# swizzle.net
KiCad netlist of a schematic drawn in EAGLE
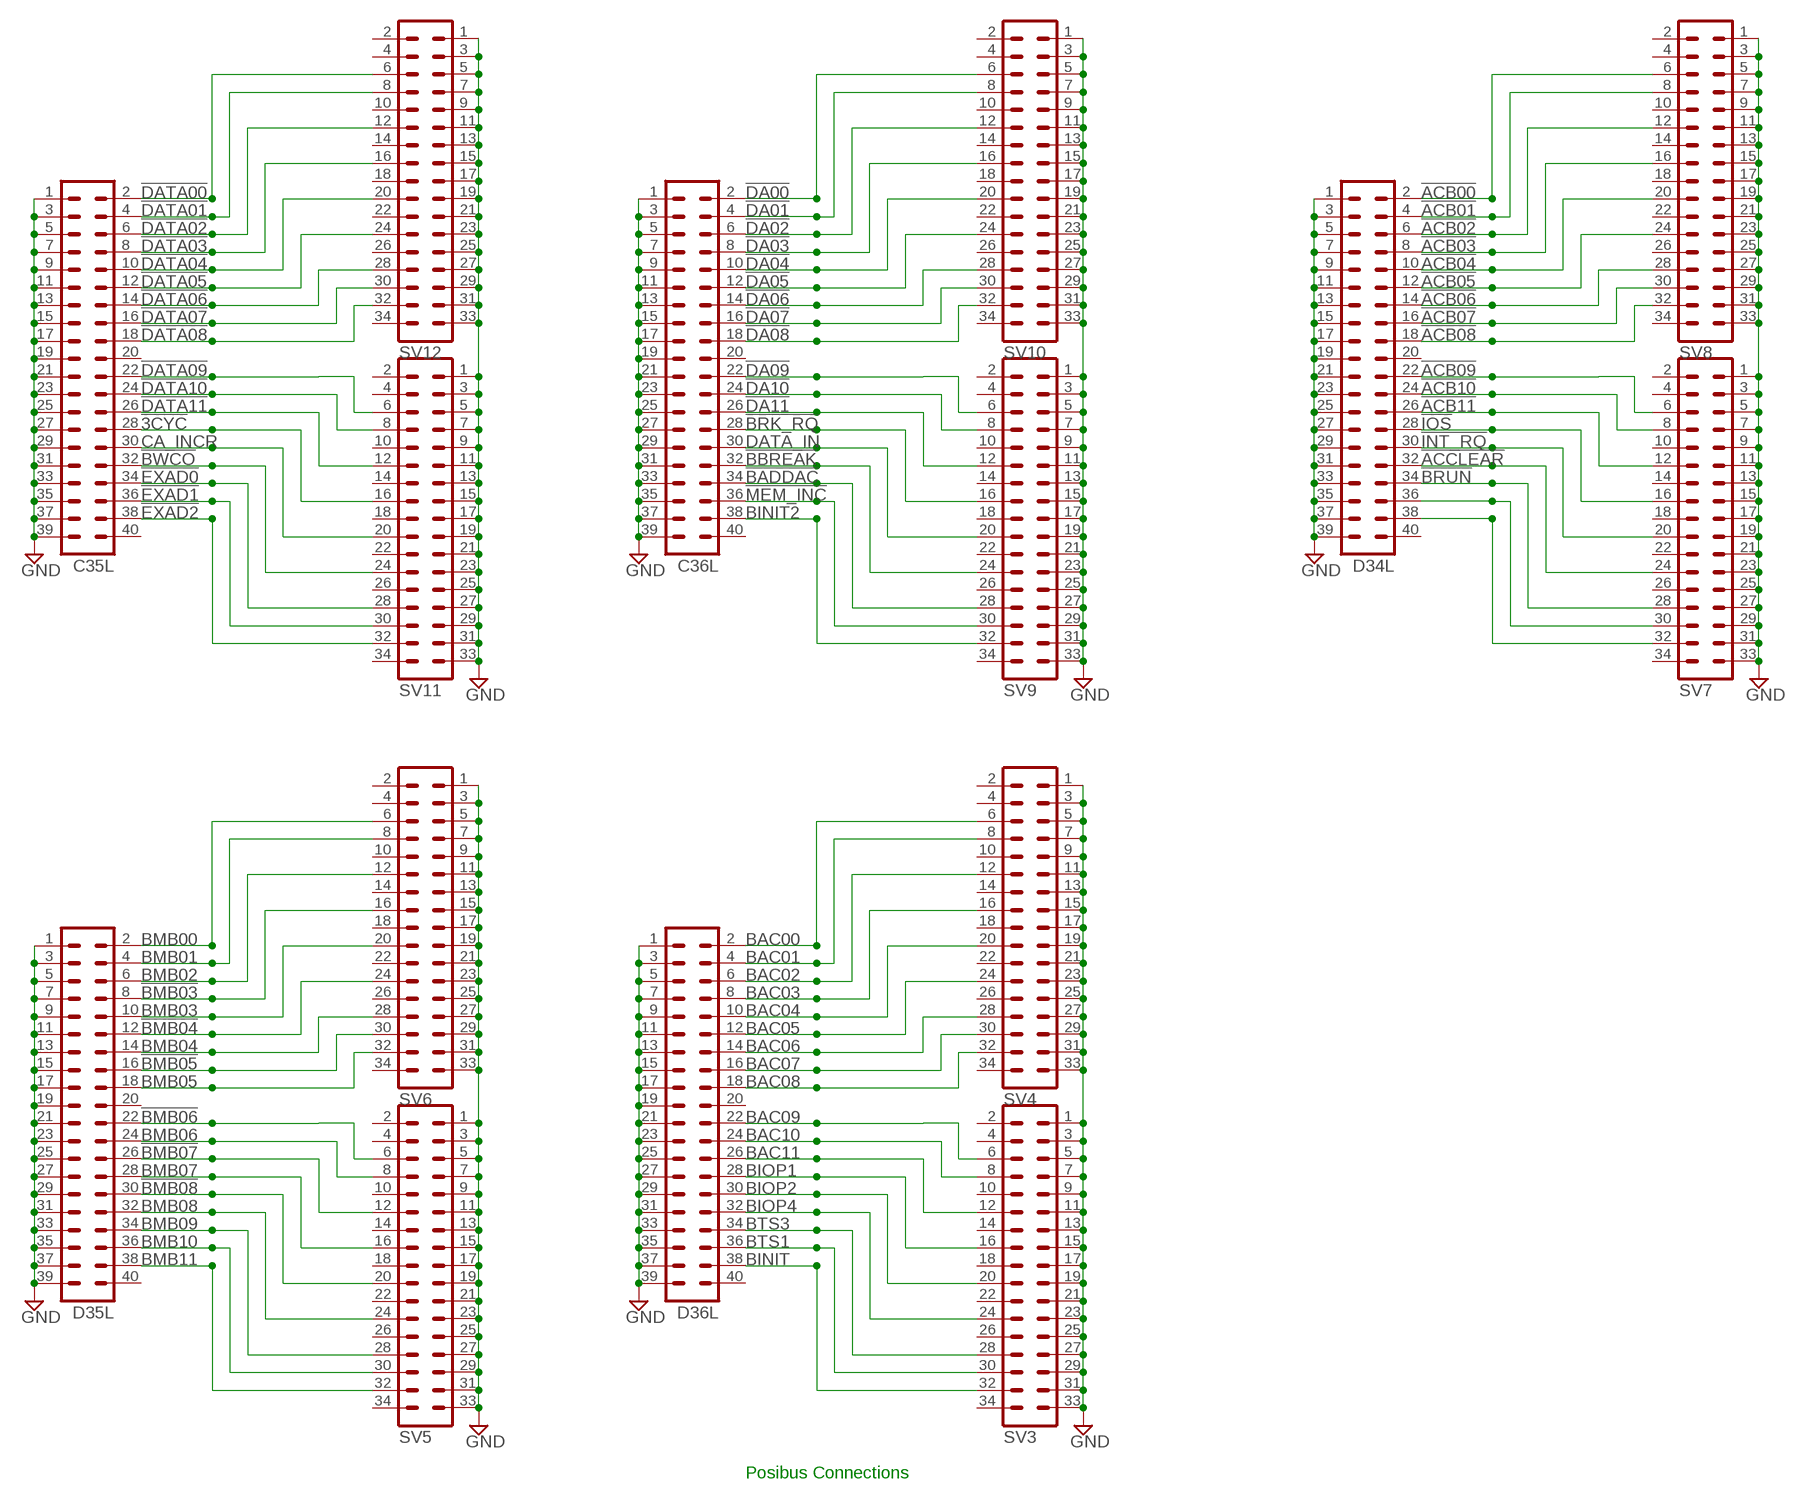
[diagram p0: schematic, sheet 1]

(export (version "E")
  (design (tool "Eeschema 10.0.6"))
  (components
    (comp (ref "C35L")
      (value "MA20-2")
      (footprint "eagle-import:MA20-2")
      (libsource (lib "eagle-import") (part "MA20-2"))
    )
    (comp (ref "C36L")
      (value "MA20-2")
      (footprint "eagle-import:MA20-2")
      (libsource (lib "eagle-import") (part "MA20-2"))
    )
    (comp (ref "D34L")
      (value "MA20-2")
      (footprint "eagle-import:MA20-2")
      (libsource (lib "eagle-import") (part "MA20-2"))
    )
    (comp (ref "D35L")
      (value "MA20-2")
      (footprint "eagle-import:MA20-2")
      (libsource (lib "eagle-import") (part "MA20-2"))
    )
    (comp (ref "D36L")
      (value "MA20-2")
      (footprint "eagle-import:MA20-2")
      (libsource (lib "eagle-import") (part "MA20-2"))
    )
    (comp (ref "SV3")
      (value "MA17-2")
      (footprint "eagle-import:MA17-2")
      (libsource (lib "eagle-import") (part "MA17-2"))
    )
    (comp (ref "SV4")
      (value "MA17-2")
      (footprint "eagle-import:MA17-2")
      (libsource (lib "eagle-import") (part "MA17-2"))
    )
    (comp (ref "SV5")
      (value "MA17-2")
      (footprint "eagle-import:MA17-2")
      (libsource (lib "eagle-import") (part "MA17-2"))
    )
    (comp (ref "SV6")
      (value "MA17-2")
      (footprint "eagle-import:MA17-2")
      (libsource (lib "eagle-import") (part "MA17-2"))
    )
    (comp (ref "SV7")
      (value "MA17-2")
      (footprint "eagle-import:MA17-2")
      (libsource (lib "eagle-import") (part "MA17-2"))
    )
    (comp (ref "SV8")
      (value "MA17-2")
      (footprint "eagle-import:MA17-2")
      (libsource (lib "eagle-import") (part "MA17-2"))
    )
    (comp (ref "SV9")
      (value "MA17-2")
      (footprint "eagle-import:MA17-2")
      (libsource (lib "eagle-import") (part "MA17-2"))
    )
    (comp (ref "SV10")
      (value "MA17-2")
      (footprint "eagle-import:MA17-2")
      (libsource (lib "eagle-import") (part "MA17-2"))
    )
    (comp (ref "SV11")
      (value "MA17-2")
      (footprint "eagle-import:MA17-2")
      (libsource (lib "eagle-import") (part "MA17-2"))
    )
    (comp (ref "SV12")
      (value "MA17-2")
      (footprint "eagle-import:MA17-2")
      (libsource (lib "eagle-import") (part "MA17-2"))
    )
  )
  (nets
    (net (code "1") (name "/BAC00") (class "Default")
      (node (ref "D36L") (pin "2") (pinfunction "2_2") (pintype "passive"))
      (node (ref "SV4") (pin "6") (pinfunction "6_6") (pintype "passive"))
    )
    (net (code "2") (name "/BAC01") (class "Default")
      (node (ref "D36L") (pin "4") (pinfunction "4_4") (pintype "passive"))
      (node (ref "SV4") (pin "8") (pinfunction "8_8") (pintype "passive"))
    )
    (net (code "3") (name "/BAC02") (class "Default")
      (node (ref "D36L") (pin "6") (pinfunction "6_6") (pintype "passive"))
      (node (ref "SV4") (pin "12") (pinfunction "12_12") (pintype "passive"))
    )
    (net (code "4") (name "/BAC03") (class "Default")
      (node (ref "D36L") (pin "8") (pinfunction "8_8") (pintype "passive"))
      (node (ref "SV4") (pin "16") (pinfunction "16_16") (pintype "passive"))
    )
    (net (code "5") (name "/BAC04") (class "Default")
      (node (ref "D36L") (pin "10") (pinfunction "10_10") (pintype "passive"))
      (node (ref "SV4") (pin "20") (pinfunction "20_20") (pintype "passive"))
    )
    (net (code "6") (name "/BAC05") (class "Default")
      (node (ref "D36L") (pin "12") (pinfunction "12_12") (pintype "passive"))
      (node (ref "SV4") (pin "24") (pinfunction "24_24") (pintype "passive"))
    )
    (net (code "7") (name "/BAC06") (class "Default")
      (node (ref "D36L") (pin "14") (pinfunction "14_14") (pintype "passive"))
      (node (ref "SV4") (pin "28") (pinfunction "28_28") (pintype "passive"))
    )
    (net (code "8") (name "/BAC07") (class "Default")
      (node (ref "D36L") (pin "16") (pinfunction "16_16") (pintype "passive"))
      (node (ref "SV4") (pin "30") (pinfunction "30_30") (pintype "passive"))
    )
    (net (code "9") (name "/BAC08") (class "Default")
      (node (ref "D36L") (pin "18") (pinfunction "18_18") (pintype "passive"))
      (node (ref "SV4") (pin "32") (pinfunction "32_32") (pintype "passive"))
    )
    (net (code "10") (name "/BAC09") (class "Default")
      (node (ref "D36L") (pin "22") (pinfunction "22_22") (pintype "passive"))
      (node (ref "SV3") (pin "6") (pinfunction "6_6") (pintype "passive"))
    )
    (net (code "11") (name "/BAC10") (class "Default")
      (node (ref "D36L") (pin "24") (pinfunction "24_24") (pintype "passive"))
      (node (ref "SV3") (pin "8") (pinfunction "8_8") (pintype "passive"))
    )
    (net (code "12") (name "/BAC11") (class "Default")
      (node (ref "D36L") (pin "26") (pinfunction "26_26") (pintype "passive"))
      (node (ref "SV3") (pin "12") (pinfunction "12_12") (pintype "passive"))
    )
    (net (code "13") (name "/BINIT") (class "Default")
      (node (ref "D36L") (pin "38") (pinfunction "38_38") (pintype "passive"))
      (node (ref "SV3") (pin "32") (pinfunction "32_32") (pintype "passive"))
    )
    (net (code "14") (name "/BINIT2") (class "Default")
      (node (ref "C36L") (pin "38") (pinfunction "38_38") (pintype "passive"))
      (node (ref "SV9") (pin "32") (pinfunction "32_32") (pintype "passive"))
    )
    (net (code "15") (name "/BIOP1") (class "Default")
      (node (ref "D36L") (pin "28") (pinfunction "28_28") (pintype "passive"))
      (node (ref "SV3") (pin "16") (pinfunction "16_16") (pintype "passive"))
    )
    (net (code "16") (name "/BIOP2") (class "Default")
      (node (ref "D36L") (pin "30") (pinfunction "30_30") (pintype "passive"))
      (node (ref "SV3") (pin "20") (pinfunction "20_20") (pintype "passive"))
    )
    (net (code "17") (name "/BIOP4") (class "Default")
      (node (ref "D36L") (pin "32") (pinfunction "32_32") (pintype "passive"))
      (node (ref "SV3") (pin "24") (pinfunction "24_24") (pintype "passive"))
    )
    (net (code "18") (name "/BMB00") (class "Default")
      (node (ref "D35L") (pin "2") (pinfunction "2_2") (pintype "passive"))
      (node (ref "SV6") (pin "6") (pinfunction "6_6") (pintype "passive"))
    )
    (net (code "19") (name "/BMB01") (class "Default")
      (node (ref "D35L") (pin "4") (pinfunction "4_4") (pintype "passive"))
      (node (ref "SV6") (pin "8") (pinfunction "8_8") (pintype "passive"))
    )
    (net (code "20") (name "/BMB02") (class "Default")
      (node (ref "D35L") (pin "6") (pinfunction "6_6") (pintype "passive"))
      (node (ref "SV6") (pin "12") (pinfunction "12_12") (pintype "passive"))
    )
    (net (code "21") (name "/BMB03") (class "Default")
      (node (ref "D35L") (pin "10") (pinfunction "10_10") (pintype "passive"))
      (node (ref "SV6") (pin "20") (pinfunction "20_20") (pintype "passive"))
    )
    (net (code "22") (name "/BMB04") (class "Default")
      (node (ref "D35L") (pin "14") (pinfunction "14_14") (pintype "passive"))
      (node (ref "SV6") (pin "28") (pinfunction "28_28") (pintype "passive"))
    )
    (net (code "23") (name "/BMB05") (class "Default")
      (node (ref "D35L") (pin "18") (pinfunction "18_18") (pintype "passive"))
      (node (ref "SV6") (pin "32") (pinfunction "32_32") (pintype "passive"))
    )
    (net (code "24") (name "/BMB06") (class "Default")
      (node (ref "D35L") (pin "24") (pinfunction "24_24") (pintype "passive"))
      (node (ref "SV5") (pin "8") (pinfunction "8_8") (pintype "passive"))
    )
    (net (code "25") (name "/BMB07") (class "Default")
      (node (ref "D35L") (pin "28") (pinfunction "28_28") (pintype "passive"))
      (node (ref "SV5") (pin "16") (pinfunction "16_16") (pintype "passive"))
    )
    (net (code "26") (name "/BMB08") (class "Default")
      (node (ref "D35L") (pin "32") (pinfunction "32_32") (pintype "passive"))
      (node (ref "SV5") (pin "24") (pinfunction "24_24") (pintype "passive"))
    )
    (net (code "27") (name "/BMB09") (class "Default")
      (node (ref "D35L") (pin "34") (pinfunction "34_34") (pintype "passive"))
      (node (ref "SV5") (pin "28") (pinfunction "28_28") (pintype "passive"))
    )
    (net (code "28") (name "/BMB10") (class "Default")
      (node (ref "D35L") (pin "36") (pinfunction "36_36") (pintype "passive"))
      (node (ref "SV5") (pin "30") (pinfunction "30_30") (pintype "passive"))
    )
    (net (code "29") (name "/BMB11") (class "Default")
      (node (ref "D35L") (pin "38") (pinfunction "38_38") (pintype "passive"))
      (node (ref "SV5") (pin "32") (pinfunction "32_32") (pintype "passive"))
    )
    (net (code "30") (name "/BTS1") (class "Default")
      (node (ref "D36L") (pin "36") (pinfunction "36_36") (pintype "passive"))
      (node (ref "SV3") (pin "30") (pinfunction "30_30") (pintype "passive"))
    )
    (net (code "31") (name "/BTS3") (class "Default")
      (node (ref "D36L") (pin "34") (pinfunction "34_34") (pintype "passive"))
      (node (ref "SV3") (pin "28") (pinfunction "28_28") (pintype "passive"))
    )
    (net (code "32") (name "/CA_INCR") (class "Default")
      (node (ref "C35L") (pin "30") (pinfunction "30_30") (pintype "passive"))
      (node (ref "SV11") (pin "20") (pinfunction "20_20") (pintype "passive"))
    )
    (net (code "33") (name "/DATA_IN") (class "Default")
      (node (ref "C36L") (pin "30") (pinfunction "30_30") (pintype "passive"))
      (node (ref "SV9") (pin "20") (pinfunction "20_20") (pintype "passive"))
    )
    (net (code "34") (name "/~{3CYC}") (class "Default")
      (node (ref "C35L") (pin "28") (pinfunction "28_28") (pintype "passive"))
      (node (ref "SV11") (pin "16") (pinfunction "16_16") (pintype "passive"))
    )
    (net (code "35") (name "/~{ACB00}") (class "Default")
      (node (ref "D34L") (pin "2") (pinfunction "2_2") (pintype "passive"))
      (node (ref "SV8") (pin "6") (pinfunction "6_6") (pintype "passive"))
    )
    (net (code "36") (name "/~{ACB01}") (class "Default")
      (node (ref "D34L") (pin "4") (pinfunction "4_4") (pintype "passive"))
      (node (ref "SV8") (pin "8") (pinfunction "8_8") (pintype "passive"))
    )
    (net (code "37") (name "/~{ACB02}") (class "Default")
      (node (ref "D34L") (pin "6") (pinfunction "6_6") (pintype "passive"))
      (node (ref "SV8") (pin "12") (pinfunction "12_12") (pintype "passive"))
    )
    (net (code "38") (name "/~{ACB03}") (class "Default")
      (node (ref "D34L") (pin "8") (pinfunction "8_8") (pintype "passive"))
      (node (ref "SV8") (pin "16") (pinfunction "16_16") (pintype "passive"))
    )
    (net (code "39") (name "/~{ACB04}") (class "Default")
      (node (ref "D34L") (pin "10") (pinfunction "10_10") (pintype "passive"))
      (node (ref "SV8") (pin "20") (pinfunction "20_20") (pintype "passive"))
    )
    (net (code "40") (name "/~{ACB05}") (class "Default")
      (node (ref "D34L") (pin "12") (pinfunction "12_12") (pintype "passive"))
      (node (ref "SV8") (pin "24") (pinfunction "24_24") (pintype "passive"))
    )
    (net (code "41") (name "/~{ACB06}") (class "Default")
      (node (ref "D34L") (pin "14") (pinfunction "14_14") (pintype "passive"))
      (node (ref "SV8") (pin "28") (pinfunction "28_28") (pintype "passive"))
    )
    (net (code "42") (name "/~{ACB07}") (class "Default")
      (node (ref "D34L") (pin "16") (pinfunction "16_16") (pintype "passive"))
      (node (ref "SV8") (pin "30") (pinfunction "30_30") (pintype "passive"))
    )
    (net (code "43") (name "/~{ACB08}") (class "Default")
      (node (ref "D34L") (pin "18") (pinfunction "18_18") (pintype "passive"))
      (node (ref "SV8") (pin "32") (pinfunction "32_32") (pintype "passive"))
    )
    (net (code "44") (name "/~{ACB09}") (class "Default")
      (node (ref "D34L") (pin "22") (pinfunction "22_22") (pintype "passive"))
      (node (ref "SV7") (pin "6") (pinfunction "6_6") (pintype "passive"))
    )
    (net (code "45") (name "/~{ACB10}") (class "Default")
      (node (ref "D34L") (pin "24") (pinfunction "24_24") (pintype "passive"))
      (node (ref "SV7") (pin "8") (pinfunction "8_8") (pintype "passive"))
    )
    (net (code "46") (name "/~{ACB11}") (class "Default")
      (node (ref "D34L") (pin "26") (pinfunction "26_26") (pintype "passive"))
      (node (ref "SV7") (pin "12") (pinfunction "12_12") (pintype "passive"))
    )
    (net (code "47") (name "/~{ACCLEAR}") (class "Default")
      (node (ref "D34L") (pin "32") (pinfunction "32_32") (pintype "passive"))
      (node (ref "SV7") (pin "24") (pinfunction "24_24") (pintype "passive"))
    )
    (net (code "48") (name "/~{BADDAC}") (class "Default")
      (node (ref "C36L") (pin "34") (pinfunction "34_34") (pintype "passive"))
      (node (ref "SV9") (pin "28") (pinfunction "28_28") (pintype "passive"))
    )
    (net (code "49") (name "/~{BBREAK}") (class "Default")
      (node (ref "C36L") (pin "32") (pinfunction "32_32") (pintype "passive"))
      (node (ref "SV9") (pin "24") (pinfunction "24_24") (pintype "passive"))
    )
    (net (code "50") (name "/~{BMB03}") (class "Default")
      (node (ref "D35L") (pin "8") (pinfunction "8_8") (pintype "passive"))
      (node (ref "SV6") (pin "16") (pinfunction "16_16") (pintype "passive"))
    )
    (net (code "51") (name "/~{BMB04}") (class "Default")
      (node (ref "D35L") (pin "12") (pinfunction "12_12") (pintype "passive"))
      (node (ref "SV6") (pin "24") (pinfunction "24_24") (pintype "passive"))
    )
    (net (code "52") (name "/~{BMB05}") (class "Default")
      (node (ref "D35L") (pin "16") (pinfunction "16_16") (pintype "passive"))
      (node (ref "SV6") (pin "30") (pinfunction "30_30") (pintype "passive"))
    )
    (net (code "53") (name "/~{BMB06}") (class "Default")
      (node (ref "D35L") (pin "22") (pinfunction "22_22") (pintype "passive"))
      (node (ref "SV5") (pin "6") (pinfunction "6_6") (pintype "passive"))
    )
    (net (code "54") (name "/~{BMB07}") (class "Default")
      (node (ref "D35L") (pin "26") (pinfunction "26_26") (pintype "passive"))
      (node (ref "SV5") (pin "12") (pinfunction "12_12") (pintype "passive"))
    )
    (net (code "55") (name "/~{BMB08}") (class "Default")
      (node (ref "D35L") (pin "30") (pinfunction "30_30") (pintype "passive"))
      (node (ref "SV5") (pin "20") (pinfunction "20_20") (pintype "passive"))
    )
    (net (code "56") (name "/~{BRK_RQ}") (class "Default")
      (node (ref "C36L") (pin "28") (pinfunction "28_28") (pintype "passive"))
      (node (ref "SV9") (pin "16") (pinfunction "16_16") (pintype "passive"))
    )
    (net (code "57") (name "/~{BRUN}") (class "Default")
      (node (ref "D34L") (pin "34") (pinfunction "34_34") (pintype "passive"))
      (node (ref "SV7") (pin "28") (pinfunction "28_28") (pintype "passive"))
    )
    (net (code "58") (name "/~{BWCO}") (class "Default")
      (node (ref "C35L") (pin "32") (pinfunction "32_32") (pintype "passive"))
      (node (ref "SV11") (pin "24") (pinfunction "24_24") (pintype "passive"))
    )
    (net (code "59") (name "/~{DA00}") (class "Default")
      (node (ref "C36L") (pin "2") (pinfunction "2_2") (pintype "passive"))
      (node (ref "SV10") (pin "6") (pinfunction "6_6") (pintype "passive"))
    )
    (net (code "60") (name "/~{DA01}") (class "Default")
      (node (ref "C36L") (pin "4") (pinfunction "4_4") (pintype "passive"))
      (node (ref "SV10") (pin "8") (pinfunction "8_8") (pintype "passive"))
    )
    (net (code "61") (name "/~{DA02}") (class "Default")
      (node (ref "C36L") (pin "6") (pinfunction "6_6") (pintype "passive"))
      (node (ref "SV10") (pin "12") (pinfunction "12_12") (pintype "passive"))
    )
    (net (code "62") (name "/~{DA03}") (class "Default")
      (node (ref "C36L") (pin "8") (pinfunction "8_8") (pintype "passive"))
      (node (ref "SV10") (pin "16") (pinfunction "16_16") (pintype "passive"))
    )
    (net (code "63") (name "/~{DA04}") (class "Default")
      (node (ref "C36L") (pin "10") (pinfunction "10_10") (pintype "passive"))
      (node (ref "SV10") (pin "20") (pinfunction "20_20") (pintype "passive"))
    )
    (net (code "64") (name "/~{DA05}") (class "Default")
      (node (ref "C36L") (pin "12") (pinfunction "12_12") (pintype "passive"))
      (node (ref "SV10") (pin "24") (pinfunction "24_24") (pintype "passive"))
    )
    (net (code "65") (name "/~{DA06}") (class "Default")
      (node (ref "C36L") (pin "14") (pinfunction "14_14") (pintype "passive"))
      (node (ref "SV10") (pin "28") (pinfunction "28_28") (pintype "passive"))
    )
    (net (code "66") (name "/~{DA07}") (class "Default")
      (node (ref "C36L") (pin "16") (pinfunction "16_16") (pintype "passive"))
      (node (ref "SV10") (pin "30") (pinfunction "30_30") (pintype "passive"))
    )
    (net (code "67") (name "/~{DA08}") (class "Default")
      (node (ref "C36L") (pin "18") (pinfunction "18_18") (pintype "passive"))
      (node (ref "SV10") (pin "32") (pinfunction "32_32") (pintype "passive"))
    )
    (net (code "68") (name "/~{DA09}") (class "Default")
      (node (ref "C36L") (pin "22") (pinfunction "22_22") (pintype "passive"))
      (node (ref "SV9") (pin "6") (pinfunction "6_6") (pintype "passive"))
    )
    (net (code "69") (name "/~{DA10}") (class "Default")
      (node (ref "C36L") (pin "24") (pinfunction "24_24") (pintype "passive"))
      (node (ref "SV9") (pin "8") (pinfunction "8_8") (pintype "passive"))
    )
    (net (code "70") (name "/~{DA11}") (class "Default")
      (node (ref "C36L") (pin "26") (pinfunction "26_26") (pintype "passive"))
      (node (ref "SV9") (pin "12") (pinfunction "12_12") (pintype "passive"))
    )
    (net (code "71") (name "/~{DATA00}") (class "Default")
      (node (ref "C35L") (pin "2") (pinfunction "2_2") (pintype "passive"))
      (node (ref "SV12") (pin "6") (pinfunction "6_6") (pintype "passive"))
    )
    (net (code "72") (name "/~{DATA01}") (class "Default")
      (node (ref "C35L") (pin "4") (pinfunction "4_4") (pintype "passive"))
      (node (ref "SV12") (pin "8") (pinfunction "8_8") (pintype "passive"))
    )
    (net (code "73") (name "/~{DATA02}") (class "Default")
      (node (ref "C35L") (pin "6") (pinfunction "6_6") (pintype "passive"))
      (node (ref "SV12") (pin "12") (pinfunction "12_12") (pintype "passive"))
    )
    (net (code "74") (name "/~{DATA03}") (class "Default")
      (node (ref "C35L") (pin "8") (pinfunction "8_8") (pintype "passive"))
      (node (ref "SV12") (pin "16") (pinfunction "16_16") (pintype "passive"))
    )
    (net (code "75") (name "/~{DATA04}") (class "Default")
      (node (ref "C35L") (pin "10") (pinfunction "10_10") (pintype "passive"))
      (node (ref "SV12") (pin "20") (pinfunction "20_20") (pintype "passive"))
    )
    (net (code "76") (name "/~{DATA05}") (class "Default")
      (node (ref "C35L") (pin "12") (pinfunction "12_12") (pintype "passive"))
      (node (ref "SV12") (pin "24") (pinfunction "24_24") (pintype "passive"))
    )
    (net (code "77") (name "/~{DATA06}") (class "Default")
      (node (ref "C35L") (pin "14") (pinfunction "14_14") (pintype "passive"))
      (node (ref "SV12") (pin "28") (pinfunction "28_28") (pintype "passive"))
    )
    (net (code "78") (name "/~{DATA07}") (class "Default")
      (node (ref "C35L") (pin "16") (pinfunction "16_16") (pintype "passive"))
      (node (ref "SV12") (pin "30") (pinfunction "30_30") (pintype "passive"))
    )
    (net (code "79") (name "/~{DATA08}") (class "Default")
      (node (ref "C35L") (pin "18") (pinfunction "18_18") (pintype "passive"))
      (node (ref "SV12") (pin "32") (pinfunction "32_32") (pintype "passive"))
    )
    (net (code "80") (name "/~{DATA09}") (class "Default")
      (node (ref "C35L") (pin "22") (pinfunction "22_22") (pintype "passive"))
      (node (ref "SV11") (pin "6") (pinfunction "6_6") (pintype "passive"))
    )
    (net (code "81") (name "/~{DATA10}") (class "Default")
      (node (ref "C35L") (pin "24") (pinfunction "24_24") (pintype "passive"))
      (node (ref "SV11") (pin "8") (pinfunction "8_8") (pintype "passive"))
    )
    (net (code "82") (name "/~{DATA11}") (class "Default")
      (node (ref "C35L") (pin "26") (pinfunction "26_26") (pintype "passive"))
      (node (ref "SV11") (pin "12") (pinfunction "12_12") (pintype "passive"))
    )
    (net (code "83") (name "/~{EXAD0}") (class "Default")
      (node (ref "C35L") (pin "34") (pinfunction "34_34") (pintype "passive"))
      (node (ref "SV11") (pin "28") (pinfunction "28_28") (pintype "passive"))
    )
    (net (code "84") (name "/~{EXAD1}") (class "Default")
      (node (ref "C35L") (pin "36") (pinfunction "36_36") (pintype "passive"))
      (node (ref "SV11") (pin "30") (pinfunction "30_30") (pintype "passive"))
    )
    (net (code "85") (name "/~{EXAD2}") (class "Default")
      (node (ref "C35L") (pin "38") (pinfunction "38_38") (pintype "passive"))
      (node (ref "SV11") (pin "32") (pinfunction "32_32") (pintype "passive"))
    )
    (net (code "86") (name "/~{INT_RQ}") (class "Default")
      (node (ref "D34L") (pin "30") (pinfunction "30_30") (pintype "passive"))
      (node (ref "SV7") (pin "20") (pinfunction "20_20") (pintype "passive"))
    )
    (net (code "87") (name "/~{IOS}") (class "Default")
      (node (ref "D34L") (pin "28") (pinfunction "28_28") (pintype "passive"))
      (node (ref "SV7") (pin "16") (pinfunction "16_16") (pintype "passive"))
    )
    (net (code "88") (name "/~{MEM_INC}") (class "Default")
      (node (ref "C36L") (pin "36") (pinfunction "36_36") (pintype "passive"))
      (node (ref "SV9") (pin "30") (pinfunction "30_30") (pintype "passive"))
    )
    (net (code "89") (name "GND") (class "Default")
      (node (ref "C35L") (pin "1") (pinfunction "1_1") (pintype "passive"))
      (node (ref "C35L") (pin "11") (pinfunction "11_11") (pintype "passive"))
      (node (ref "C35L") (pin "13") (pinfunction "13_13") (pintype "passive"))
      (node (ref "C35L") (pin "15") (pinfunction "15_15") (pintype "passive"))
      (node (ref "C35L") (pin "17") (pinfunction "17_17") (pintype "passive"))
      (node (ref "C35L") (pin "19") (pinfunction "19_19") (pintype "passive"))
      (node (ref "C35L") (pin "21") (pinfunction "21_21") (pintype "passive"))
      (node (ref "C35L") (pin "23") (pinfunction "23_23") (pintype "passive"))
      (node (ref "C35L") (pin "25") (pinfunction "25_25") (pintype "passive"))
      (node (ref "C35L") (pin "27") (pinfunction "27_27") (pintype "passive"))
      (node (ref "C35L") (pin "29") (pinfunction "29_29") (pintype "passive"))
      (node (ref "C35L") (pin "3") (pinfunction "3_3") (pintype "passive"))
      (node (ref "C35L") (pin "31") (pinfunction "31_31") (pintype "passive"))
      (node (ref "C35L") (pin "33") (pinfunction "33_33") (pintype "passive"))
      (node (ref "C35L") (pin "35") (pinfunction "35_35") (pintype "passive"))
      (node (ref "C35L") (pin "37") (pinfunction "37_37") (pintype "passive"))
      (node (ref "C35L") (pin "39") (pinfunction "39_39") (pintype "passive"))
      (node (ref "C35L") (pin "5") (pinfunction "5_5") (pintype "passive"))
      (node (ref "C35L") (pin "7") (pinfunction "7_7") (pintype "passive"))
      (node (ref "C35L") (pin "9") (pinfunction "9_9") (pintype "passive"))
      (node (ref "C36L") (pin "1") (pinfunction "1_1") (pintype "passive"))
      (node (ref "C36L") (pin "11") (pinfunction "11_11") (pintype "passive"))
      (node (ref "C36L") (pin "13") (pinfunction "13_13") (pintype "passive"))
      (node (ref "C36L") (pin "15") (pinfunction "15_15") (pintype "passive"))
      (node (ref "C36L") (pin "17") (pinfunction "17_17") (pintype "passive"))
      (node (ref "C36L") (pin "19") (pinfunction "19_19") (pintype "passive"))
      (node (ref "C36L") (pin "21") (pinfunction "21_21") (pintype "passive"))
      (node (ref "C36L") (pin "23") (pinfunction "23_23") (pintype "passive"))
      (node (ref "C36L") (pin "25") (pinfunction "25_25") (pintype "passive"))
      (node (ref "C36L") (pin "27") (pinfunction "27_27") (pintype "passive"))
      (node (ref "C36L") (pin "29") (pinfunction "29_29") (pintype "passive"))
      (node (ref "C36L") (pin "3") (pinfunction "3_3") (pintype "passive"))
      (node (ref "C36L") (pin "31") (pinfunction "31_31") (pintype "passive"))
      (node (ref "C36L") (pin "33") (pinfunction "33_33") (pintype "passive"))
      (node (ref "C36L") (pin "35") (pinfunction "35_35") (pintype "passive"))
      (node (ref "C36L") (pin "37") (pinfunction "37_37") (pintype "passive"))
      (node (ref "C36L") (pin "39") (pinfunction "39_39") (pintype "passive"))
      (node (ref "C36L") (pin "5") (pinfunction "5_5") (pintype "passive"))
      (node (ref "C36L") (pin "7") (pinfunction "7_7") (pintype "passive"))
      (node (ref "C36L") (pin "9") (pinfunction "9_9") (pintype "passive"))
      (node (ref "D34L") (pin "1") (pinfunction "1_1") (pintype "passive"))
      (node (ref "D34L") (pin "11") (pinfunction "11_11") (pintype "passive"))
      (node (ref "D34L") (pin "13") (pinfunction "13_13") (pintype "passive"))
      (node (ref "D34L") (pin "15") (pinfunction "15_15") (pintype "passive"))
      (node (ref "D34L") (pin "17") (pinfunction "17_17") (pintype "passive"))
      (node (ref "D34L") (pin "19") (pinfunction "19_19") (pintype "passive"))
      (node (ref "D34L") (pin "21") (pinfunction "21_21") (pintype "passive"))
      (node (ref "D34L") (pin "23") (pinfunction "23_23") (pintype "passive"))
      (node (ref "D34L") (pin "25") (pinfunction "25_25") (pintype "passive"))
      (node (ref "D34L") (pin "27") (pinfunction "27_27") (pintype "passive"))
      (node (ref "D34L") (pin "29") (pinfunction "29_29") (pintype "passive"))
      (node (ref "D34L") (pin "3") (pinfunction "3_3") (pintype "passive"))
      (node (ref "D34L") (pin "31") (pinfunction "31_31") (pintype "passive"))
      (node (ref "D34L") (pin "33") (pinfunction "33_33") (pintype "passive"))
      (node (ref "D34L") (pin "35") (pinfunction "35_35") (pintype "passive"))
      (node (ref "D34L") (pin "37") (pinfunction "37_37") (pintype "passive"))
      (node (ref "D34L") (pin "39") (pinfunction "39_39") (pintype "passive"))
      (node (ref "D34L") (pin "5") (pinfunction "5_5") (pintype "passive"))
      (node (ref "D34L") (pin "7") (pinfunction "7_7") (pintype "passive"))
      (node (ref "D34L") (pin "9") (pinfunction "9_9") (pintype "passive"))
      (node (ref "D35L") (pin "1") (pinfunction "1_1") (pintype "passive"))
      (node (ref "D35L") (pin "11") (pinfunction "11_11") (pintype "passive"))
      (node (ref "D35L") (pin "13") (pinfunction "13_13") (pintype "passive"))
      (node (ref "D35L") (pin "15") (pinfunction "15_15") (pintype "passive"))
      (node (ref "D35L") (pin "17") (pinfunction "17_17") (pintype "passive"))
      (node (ref "D35L") (pin "19") (pinfunction "19_19") (pintype "passive"))
      (node (ref "D35L") (pin "21") (pinfunction "21_21") (pintype "passive"))
      (node (ref "D35L") (pin "23") (pinfunction "23_23") (pintype "passive"))
      (node (ref "D35L") (pin "25") (pinfunction "25_25") (pintype "passive"))
      (node (ref "D35L") (pin "27") (pinfunction "27_27") (pintype "passive"))
      (node (ref "D35L") (pin "29") (pinfunction "29_29") (pintype "passive"))
      (node (ref "D35L") (pin "3") (pinfunction "3_3") (pintype "passive"))
      (node (ref "D35L") (pin "31") (pinfunction "31_31") (pintype "passive"))
      (node (ref "D35L") (pin "33") (pinfunction "33_33") (pintype "passive"))
      (node (ref "D35L") (pin "35") (pinfunction "35_35") (pintype "passive"))
      (node (ref "D35L") (pin "37") (pinfunction "37_37") (pintype "passive"))
      (node (ref "D35L") (pin "39") (pinfunction "39_39") (pintype "passive"))
      (node (ref "D35L") (pin "5") (pinfunction "5_5") (pintype "passive"))
      (node (ref "D35L") (pin "7") (pinfunction "7_7") (pintype "passive"))
      (node (ref "D35L") (pin "9") (pinfunction "9_9") (pintype "passive"))
      (node (ref "D36L") (pin "1") (pinfunction "1_1") (pintype "passive"))
      (node (ref "D36L") (pin "11") (pinfunction "11_11") (pintype "passive"))
      (node (ref "D36L") (pin "13") (pinfunction "13_13") (pintype "passive"))
      (node (ref "D36L") (pin "15") (pinfunction "15_15") (pintype "passive"))
      (node (ref "D36L") (pin "17") (pinfunction "17_17") (pintype "passive"))
      (node (ref "D36L") (pin "19") (pinfunction "19_19") (pintype "passive"))
      (node (ref "D36L") (pin "21") (pinfunction "21_21") (pintype "passive"))
      (node (ref "D36L") (pin "23") (pinfunction "23_23") (pintype "passive"))
      (node (ref "D36L") (pin "25") (pinfunction "25_25") (pintype "passive"))
      (node (ref "D36L") (pin "27") (pinfunction "27_27") (pintype "passive"))
      (node (ref "D36L") (pin "29") (pinfunction "29_29") (pintype "passive"))
      (node (ref "D36L") (pin "3") (pinfunction "3_3") (pintype "passive"))
      (node (ref "D36L") (pin "31") (pinfunction "31_31") (pintype "passive"))
      (node (ref "D36L") (pin "33") (pinfunction "33_33") (pintype "passive"))
      (node (ref "D36L") (pin "35") (pinfunction "35_35") (pintype "passive"))
      (node (ref "D36L") (pin "37") (pinfunction "37_37") (pintype "passive"))
      (node (ref "D36L") (pin "39") (pinfunction "39_39") (pintype "passive"))
      (node (ref "D36L") (pin "5") (pinfunction "5_5") (pintype "passive"))
      (node (ref "D36L") (pin "7") (pinfunction "7_7") (pintype "passive"))
      (node (ref "D36L") (pin "9") (pinfunction "9_9") (pintype "passive"))
      (node (ref "SV10") (pin "1") (pinfunction "1_1") (pintype "passive"))
      (node (ref "SV10") (pin "11") (pinfunction "11_11") (pintype "passive"))
      (node (ref "SV10") (pin "13") (pinfunction "13_13") (pintype "passive"))
      (node (ref "SV10") (pin "15") (pinfunction "15_15") (pintype "passive"))
      (node (ref "SV10") (pin "17") (pinfunction "17_17") (pintype "passive"))
      (node (ref "SV10") (pin "19") (pinfunction "19_19") (pintype "passive"))
      (node (ref "SV10") (pin "21") (pinfunction "21_21") (pintype "passive"))
      (node (ref "SV10") (pin "23") (pinfunction "23_23") (pintype "passive"))
      (node (ref "SV10") (pin "25") (pinfunction "25_25") (pintype "passive"))
      (node (ref "SV10") (pin "27") (pinfunction "27_27") (pintype "passive"))
      (node (ref "SV10") (pin "29") (pinfunction "29_29") (pintype "passive"))
      (node (ref "SV10") (pin "3") (pinfunction "3_3") (pintype "passive"))
      (node (ref "SV10") (pin "31") (pinfunction "31_31") (pintype "passive"))
      (node (ref "SV10") (pin "33") (pinfunction "33_33") (pintype "passive"))
      (node (ref "SV10") (pin "5") (pinfunction "5_5") (pintype "passive"))
      (node (ref "SV10") (pin "7") (pinfunction "7_7") (pintype "passive"))
      (node (ref "SV10") (pin "9") (pinfunction "9_9") (pintype "passive"))
      (node (ref "SV11") (pin "1") (pinfunction "1_1") (pintype "passive"))
      (node (ref "SV11") (pin "11") (pinfunction "11_11") (pintype "passive"))
      (node (ref "SV11") (pin "13") (pinfunction "13_13") (pintype "passive"))
      (node (ref "SV11") (pin "15") (pinfunction "15_15") (pintype "passive"))
      (node (ref "SV11") (pin "17") (pinfunction "17_17") (pintype "passive"))
      (node (ref "SV11") (pin "19") (pinfunction "19_19") (pintype "passive"))
      (node (ref "SV11") (pin "21") (pinfunction "21_21") (pintype "passive"))
      (node (ref "SV11") (pin "23") (pinfunction "23_23") (pintype "passive"))
      (node (ref "SV11") (pin "25") (pinfunction "25_25") (pintype "passive"))
      (node (ref "SV11") (pin "27") (pinfunction "27_27") (pintype "passive"))
      (node (ref "SV11") (pin "29") (pinfunction "29_29") (pintype "passive"))
      (node (ref "SV11") (pin "3") (pinfunction "3_3") (pintype "passive"))
      (node (ref "SV11") (pin "31") (pinfunction "31_31") (pintype "passive"))
      (node (ref "SV11") (pin "33") (pinfunction "33_33") (pintype "passive"))
      (node (ref "SV11") (pin "5") (pinfunction "5_5") (pintype "passive"))
      (node (ref "SV11") (pin "7") (pinfunction "7_7") (pintype "passive"))
      (node (ref "SV11") (pin "9") (pinfunction "9_9") (pintype "passive"))
      (node (ref "SV12") (pin "1") (pinfunction "1_1") (pintype "passive"))
      (node (ref "SV12") (pin "11") (pinfunction "11_11") (pintype "passive"))
      (node (ref "SV12") (pin "13") (pinfunction "13_13") (pintype "passive"))
      (node (ref "SV12") (pin "15") (pinfunction "15_15") (pintype "passive"))
      (node (ref "SV12") (pin "17") (pinfunction "17_17") (pintype "passive"))
      (node (ref "SV12") (pin "19") (pinfunction "19_19") (pintype "passive"))
      (node (ref "SV12") (pin "21") (pinfunction "21_21") (pintype "passive"))
      (node (ref "SV12") (pin "23") (pinfunction "23_23") (pintype "passive"))
      (node (ref "SV12") (pin "25") (pinfunction "25_25") (pintype "passive"))
      (node (ref "SV12") (pin "27") (pinfunction "27_27") (pintype "passive"))
      (node (ref "SV12") (pin "29") (pinfunction "29_29") (pintype "passive"))
      (node (ref "SV12") (pin "3") (pinfunction "3_3") (pintype "passive"))
      (node (ref "SV12") (pin "31") (pinfunction "31_31") (pintype "passive"))
      (node (ref "SV12") (pin "33") (pinfunction "33_33") (pintype "passive"))
      (node (ref "SV12") (pin "5") (pinfunction "5_5") (pintype "passive"))
      (node (ref "SV12") (pin "7") (pinfunction "7_7") (pintype "passive"))
      (node (ref "SV12") (pin "9") (pinfunction "9_9") (pintype "passive"))
      (node (ref "SV3") (pin "1") (pinfunction "1_1") (pintype "passive"))
      (node (ref "SV3") (pin "11") (pinfunction "11_11") (pintype "passive"))
      (node (ref "SV3") (pin "13") (pinfunction "13_13") (pintype "passive"))
      (node (ref "SV3") (pin "15") (pinfunction "15_15") (pintype "passive"))
      (node (ref "SV3") (pin "17") (pinfunction "17_17") (pintype "passive"))
      (node (ref "SV3") (pin "19") (pinfunction "19_19") (pintype "passive"))
      (node (ref "SV3") (pin "21") (pinfunction "21_21") (pintype "passive"))
      (node (ref "SV3") (pin "23") (pinfunction "23_23") (pintype "passive"))
      (node (ref "SV3") (pin "25") (pinfunction "25_25") (pintype "passive"))
      (node (ref "SV3") (pin "27") (pinfunction "27_27") (pintype "passive"))
      (node (ref "SV3") (pin "29") (pinfunction "29_29") (pintype "passive"))
      (node (ref "SV3") (pin "3") (pinfunction "3_3") (pintype "passive"))
      (node (ref "SV3") (pin "31") (pinfunction "31_31") (pintype "passive"))
      (node (ref "SV3") (pin "33") (pinfunction "33_33") (pintype "passive"))
      (node (ref "SV3") (pin "5") (pinfunction "5_5") (pintype "passive"))
      (node (ref "SV3") (pin "7") (pinfunction "7_7") (pintype "passive"))
      (node (ref "SV3") (pin "9") (pinfunction "9_9") (pintype "passive"))
      (node (ref "SV4") (pin "1") (pinfunction "1_1") (pintype "passive"))
      (node (ref "SV4") (pin "11") (pinfunction "11_11") (pintype "passive"))
      (node (ref "SV4") (pin "13") (pinfunction "13_13") (pintype "passive"))
      (node (ref "SV4") (pin "15") (pinfunction "15_15") (pintype "passive"))
      (node (ref "SV4") (pin "17") (pinfunction "17_17") (pintype "passive"))
      (node (ref "SV4") (pin "19") (pinfunction "19_19") (pintype "passive"))
      (node (ref "SV4") (pin "21") (pinfunction "21_21") (pintype "passive"))
      (node (ref "SV4") (pin "23") (pinfunction "23_23") (pintype "passive"))
      (node (ref "SV4") (pin "25") (pinfunction "25_25") (pintype "passive"))
      (node (ref "SV4") (pin "27") (pinfunction "27_27") (pintype "passive"))
      (node (ref "SV4") (pin "29") (pinfunction "29_29") (pintype "passive"))
      (node (ref "SV4") (pin "3") (pinfunction "3_3") (pintype "passive"))
      (node (ref "SV4") (pin "31") (pinfunction "31_31") (pintype "passive"))
      (node (ref "SV4") (pin "33") (pinfunction "33_33") (pintype "passive"))
      (node (ref "SV4") (pin "5") (pinfunction "5_5") (pintype "passive"))
      (node (ref "SV4") (pin "7") (pinfunction "7_7") (pintype "passive"))
      (node (ref "SV4") (pin "9") (pinfunction "9_9") (pintype "passive"))
      (node (ref "SV5") (pin "1") (pinfunction "1_1") (pintype "passive"))
      (node (ref "SV5") (pin "11") (pinfunction "11_11") (pintype "passive"))
      (node (ref "SV5") (pin "13") (pinfunction "13_13") (pintype "passive"))
      (node (ref "SV5") (pin "15") (pinfunction "15_15") (pintype "passive"))
      (node (ref "SV5") (pin "17") (pinfunction "17_17") (pintype "passive"))
      (node (ref "SV5") (pin "19") (pinfunction "19_19") (pintype "passive"))
      (node (ref "SV5") (pin "21") (pinfunction "21_21") (pintype "passive"))
      (node (ref "SV5") (pin "23") (pinfunction "23_23") (pintype "passive"))
      (node (ref "SV5") (pin "25") (pinfunction "25_25") (pintype "passive"))
      (node (ref "SV5") (pin "27") (pinfunction "27_27") (pintype "passive"))
      (node (ref "SV5") (pin "29") (pinfunction "29_29") (pintype "passive"))
      (node (ref "SV5") (pin "3") (pinfunction "3_3") (pintype "passive"))
      (node (ref "SV5") (pin "31") (pinfunction "31_31") (pintype "passive"))
      (node (ref "SV5") (pin "33") (pinfunction "33_33") (pintype "passive"))
      (node (ref "SV5") (pin "5") (pinfunction "5_5") (pintype "passive"))
      (node (ref "SV5") (pin "7") (pinfunction "7_7") (pintype "passive"))
      (node (ref "SV5") (pin "9") (pinfunction "9_9") (pintype "passive"))
      (node (ref "SV6") (pin "1") (pinfunction "1_1") (pintype "passive"))
      (node (ref "SV6") (pin "11") (pinfunction "11_11") (pintype "passive"))
      (node (ref "SV6") (pin "13") (pinfunction "13_13") (pintype "passive"))
      (node (ref "SV6") (pin "15") (pinfunction "15_15") (pintype "passive"))
      (node (ref "SV6") (pin "17") (pinfunction "17_17") (pintype "passive"))
      (node (ref "SV6") (pin "19") (pinfunction "19_19") (pintype "passive"))
      (node (ref "SV6") (pin "21") (pinfunction "21_21") (pintype "passive"))
      (node (ref "SV6") (pin "23") (pinfunction "23_23") (pintype "passive"))
      (node (ref "SV6") (pin "25") (pinfunction "25_25") (pintype "passive"))
      (node (ref "SV6") (pin "27") (pinfunction "27_27") (pintype "passive"))
      (node (ref "SV6") (pin "29") (pinfunction "29_29") (pintype "passive"))
      (node (ref "SV6") (pin "3") (pinfunction "3_3") (pintype "passive"))
      (node (ref "SV6") (pin "31") (pinfunction "31_31") (pintype "passive"))
      (node (ref "SV6") (pin "33") (pinfunction "33_33") (pintype "passive"))
      (node (ref "SV6") (pin "5") (pinfunction "5_5") (pintype "passive"))
      (node (ref "SV6") (pin "7") (pinfunction "7_7") (pintype "passive"))
      (node (ref "SV6") (pin "9") (pinfunction "9_9") (pintype "passive"))
      (node (ref "SV7") (pin "1") (pinfunction "1_1") (pintype "passive"))
      (node (ref "SV7") (pin "11") (pinfunction "11_11") (pintype "passive"))
      (node (ref "SV7") (pin "13") (pinfunction "13_13") (pintype "passive"))
      (node (ref "SV7") (pin "15") (pinfunction "15_15") (pintype "passive"))
      (node (ref "SV7") (pin "17") (pinfunction "17_17") (pintype "passive"))
      (node (ref "SV7") (pin "19") (pinfunction "19_19") (pintype "passive"))
      (node (ref "SV7") (pin "21") (pinfunction "21_21") (pintype "passive"))
      (node (ref "SV7") (pin "23") (pinfunction "23_23") (pintype "passive"))
      (node (ref "SV7") (pin "25") (pinfunction "25_25") (pintype "passive"))
      (node (ref "SV7") (pin "27") (pinfunction "27_27") (pintype "passive"))
      (node (ref "SV7") (pin "29") (pinfunction "29_29") (pintype "passive"))
      (node (ref "SV7") (pin "3") (pinfunction "3_3") (pintype "passive"))
      (node (ref "SV7") (pin "31") (pinfunction "31_31") (pintype "passive"))
      (node (ref "SV7") (pin "33") (pinfunction "33_33") (pintype "passive"))
      (node (ref "SV7") (pin "5") (pinfunction "5_5") (pintype "passive"))
      (node (ref "SV7") (pin "7") (pinfunction "7_7") (pintype "passive"))
      (node (ref "SV7") (pin "9") (pinfunction "9_9") (pintype "passive"))
      (node (ref "SV8") (pin "1") (pinfunction "1_1") (pintype "passive"))
      (node (ref "SV8") (pin "11") (pinfunction "11_11") (pintype "passive"))
      (node (ref "SV8") (pin "13") (pinfunction "13_13") (pintype "passive"))
      (node (ref "SV8") (pin "15") (pinfunction "15_15") (pintype "passive"))
      (node (ref "SV8") (pin "17") (pinfunction "17_17") (pintype "passive"))
      (node (ref "SV8") (pin "19") (pinfunction "19_19") (pintype "passive"))
      (node (ref "SV8") (pin "21") (pinfunction "21_21") (pintype "passive"))
      (node (ref "SV8") (pin "23") (pinfunction "23_23") (pintype "passive"))
      (node (ref "SV8") (pin "25") (pinfunction "25_25") (pintype "passive"))
      (node (ref "SV8") (pin "27") (pinfunction "27_27") (pintype "passive"))
      (node (ref "SV8") (pin "29") (pinfunction "29_29") (pintype "passive"))
      (node (ref "SV8") (pin "3") (pinfunction "3_3") (pintype "passive"))
      (node (ref "SV8") (pin "31") (pinfunction "31_31") (pintype "passive"))
      (node (ref "SV8") (pin "33") (pinfunction "33_33") (pintype "passive"))
      (node (ref "SV8") (pin "5") (pinfunction "5_5") (pintype "passive"))
      (node (ref "SV8") (pin "7") (pinfunction "7_7") (pintype "passive"))
      (node (ref "SV8") (pin "9") (pinfunction "9_9") (pintype "passive"))
      (node (ref "SV9") (pin "1") (pinfunction "1_1") (pintype "passive"))
      (node (ref "SV9") (pin "11") (pinfunction "11_11") (pintype "passive"))
      (node (ref "SV9") (pin "13") (pinfunction "13_13") (pintype "passive"))
      (node (ref "SV9") (pin "15") (pinfunction "15_15") (pintype "passive"))
      (node (ref "SV9") (pin "17") (pinfunction "17_17") (pintype "passive"))
      (node (ref "SV9") (pin "19") (pinfunction "19_19") (pintype "passive"))
      (node (ref "SV9") (pin "21") (pinfunction "21_21") (pintype "passive"))
      (node (ref "SV9") (pin "23") (pinfunction "23_23") (pintype "passive"))
      (node (ref "SV9") (pin "25") (pinfunction "25_25") (pintype "passive"))
      (node (ref "SV9") (pin "27") (pinfunction "27_27") (pintype "passive"))
      (node (ref "SV9") (pin "29") (pinfunction "29_29") (pintype "passive"))
      (node (ref "SV9") (pin "3") (pinfunction "3_3") (pintype "passive"))
      (node (ref "SV9") (pin "31") (pinfunction "31_31") (pintype "passive"))
      (node (ref "SV9") (pin "33") (pinfunction "33_33") (pintype "passive"))
      (node (ref "SV9") (pin "5") (pinfunction "5_5") (pintype "passive"))
      (node (ref "SV9") (pin "7") (pinfunction "7_7") (pintype "passive"))
      (node (ref "SV9") (pin "9") (pinfunction "9_9") (pintype "passive"))
    )
    (net (code "90") (name "Net-(D34L-Pad36)") (class "Default")
      (node (ref "D34L") (pin "36") (pinfunction "36_36") (pintype "passive"))
      (node (ref "SV7") (pin "30") (pinfunction "30_30") (pintype "passive"))
    )
    (net (code "91") (name "Net-(D34L-Pad38)") (class "Default")
      (node (ref "D34L") (pin "38") (pinfunction "38_38") (pintype "passive"))
      (node (ref "SV7") (pin "32") (pinfunction "32_32") (pintype "passive"))
    )
    (net (code "92") (name "unconnected-(C35L-Pad20)") (class "Default")
      (node (ref "C35L") (pin "20") (pinfunction "20_20") (pintype "passive"))
    )
    (net (code "93") (name "unconnected-(C35L-Pad40)") (class "Default")
      (node (ref "C35L") (pin "40") (pinfunction "40_40") (pintype "passive"))
    )
    (net (code "94") (name "unconnected-(C36L-Pad20)") (class "Default")
      (node (ref "C36L") (pin "20") (pinfunction "20_20") (pintype "passive"))
    )
    (net (code "95") (name "unconnected-(C36L-Pad40)") (class "Default")
      (node (ref "C36L") (pin "40") (pinfunction "40_40") (pintype "passive"))
    )
    (net (code "96") (name "unconnected-(D34L-Pad20)") (class "Default")
      (node (ref "D34L") (pin "20") (pinfunction "20_20") (pintype "passive"))
    )
    (net (code "97") (name "unconnected-(D34L-Pad40)") (class "Default")
      (node (ref "D34L") (pin "40") (pinfunction "40_40") (pintype "passive"))
    )
    (net (code "98") (name "unconnected-(D35L-Pad20)") (class "Default")
      (node (ref "D35L") (pin "20") (pinfunction "20_20") (pintype "passive"))
    )
    (net (code "99") (name "unconnected-(D35L-Pad40)") (class "Default")
      (node (ref "D35L") (pin "40") (pinfunction "40_40") (pintype "passive"))
    )
    (net (code "100") (name "unconnected-(D36L-Pad20)") (class "Default")
      (node (ref "D36L") (pin "20") (pinfunction "20_20") (pintype "passive"))
    )
    (net (code "101") (name "unconnected-(D36L-Pad40)") (class "Default")
      (node (ref "D36L") (pin "40") (pinfunction "40_40") (pintype "passive"))
    )
    (net (code "102") (name "unconnected-(SV3-Pad2)") (class "Default")
      (node (ref "SV3") (pin "2") (pinfunction "2_2") (pintype "passive"))
    )
    (net (code "103") (name "unconnected-(SV3-Pad4)") (class "Default")
      (node (ref "SV3") (pin "4") (pinfunction "4_4") (pintype "passive"))
    )
    (net (code "104") (name "unconnected-(SV3-Pad10)") (class "Default")
      (node (ref "SV3") (pin "10") (pinfunction "10_10") (pintype "passive"))
    )
    (net (code "105") (name "unconnected-(SV3-Pad14)") (class "Default")
      (node (ref "SV3") (pin "14") (pinfunction "14_14") (pintype "passive"))
    )
    (net (code "106") (name "unconnected-(SV3-Pad18)") (class "Default")
      (node (ref "SV3") (pin "18") (pinfunction "18_18") (pintype "passive"))
    )
    (net (code "107") (name "unconnected-(SV3-Pad22)") (class "Default")
      (node (ref "SV3") (pin "22") (pinfunction "22_22") (pintype "passive"))
    )
    (net (code "108") (name "unconnected-(SV3-Pad26)") (class "Default")
      (node (ref "SV3") (pin "26") (pinfunction "26_26") (pintype "passive"))
    )
    (net (code "109") (name "unconnected-(SV3-Pad34)") (class "Default")
      (node (ref "SV3") (pin "34") (pinfunction "34_34") (pintype "passive"))
    )
    (net (code "110") (name "unconnected-(SV4-Pad2)") (class "Default")
      (node (ref "SV4") (pin "2") (pinfunction "2_2") (pintype "passive"))
    )
    (net (code "111") (name "unconnected-(SV4-Pad4)") (class "Default")
      (node (ref "SV4") (pin "4") (pinfunction "4_4") (pintype "passive"))
    )
    (net (code "112") (name "unconnected-(SV4-Pad10)") (class "Default")
      (node (ref "SV4") (pin "10") (pinfunction "10_10") (pintype "passive"))
    )
    (net (code "113") (name "unconnected-(SV4-Pad14)") (class "Default")
      (node (ref "SV4") (pin "14") (pinfunction "14_14") (pintype "passive"))
    )
    (net (code "114") (name "unconnected-(SV4-Pad18)") (class "Default")
      (node (ref "SV4") (pin "18") (pinfunction "18_18") (pintype "passive"))
    )
    (net (code "115") (name "unconnected-(SV4-Pad22)") (class "Default")
      (node (ref "SV4") (pin "22") (pinfunction "22_22") (pintype "passive"))
    )
    (net (code "116") (name "unconnected-(SV4-Pad26)") (class "Default")
      (node (ref "SV4") (pin "26") (pinfunction "26_26") (pintype "passive"))
    )
    (net (code "117") (name "unconnected-(SV4-Pad34)") (class "Default")
      (node (ref "SV4") (pin "34") (pinfunction "34_34") (pintype "passive"))
    )
    (net (code "118") (name "unconnected-(SV5-Pad2)") (class "Default")
      (node (ref "SV5") (pin "2") (pinfunction "2_2") (pintype "passive"))
    )
    (net (code "119") (name "unconnected-(SV5-Pad4)") (class "Default")
      (node (ref "SV5") (pin "4") (pinfunction "4_4") (pintype "passive"))
    )
    (net (code "120") (name "unconnected-(SV5-Pad10)") (class "Default")
      (node (ref "SV5") (pin "10") (pinfunction "10_10") (pintype "passive"))
    )
    (net (code "121") (name "unconnected-(SV5-Pad14)") (class "Default")
      (node (ref "SV5") (pin "14") (pinfunction "14_14") (pintype "passive"))
    )
    (net (code "122") (name "unconnected-(SV5-Pad18)") (class "Default")
      (node (ref "SV5") (pin "18") (pinfunction "18_18") (pintype "passive"))
    )
    (net (code "123") (name "unconnected-(SV5-Pad22)") (class "Default")
      (node (ref "SV5") (pin "22") (pinfunction "22_22") (pintype "passive"))
    )
    (net (code "124") (name "unconnected-(SV5-Pad26)") (class "Default")
      (node (ref "SV5") (pin "26") (pinfunction "26_26") (pintype "passive"))
    )
    (net (code "125") (name "unconnected-(SV5-Pad34)") (class "Default")
      (node (ref "SV5") (pin "34") (pinfunction "34_34") (pintype "passive"))
    )
    (net (code "126") (name "unconnected-(SV6-Pad2)") (class "Default")
      (node (ref "SV6") (pin "2") (pinfunction "2_2") (pintype "passive"))
    )
    (net (code "127") (name "unconnected-(SV6-Pad4)") (class "Default")
      (node (ref "SV6") (pin "4") (pinfunction "4_4") (pintype "passive"))
    )
    (net (code "128") (name "unconnected-(SV6-Pad10)") (class "Default")
      (node (ref "SV6") (pin "10") (pinfunction "10_10") (pintype "passive"))
    )
    (net (code "129") (name "unconnected-(SV6-Pad14)") (class "Default")
      (node (ref "SV6") (pin "14") (pinfunction "14_14") (pintype "passive"))
    )
    (net (code "130") (name "unconnected-(SV6-Pad18)") (class "Default")
      (node (ref "SV6") (pin "18") (pinfunction "18_18") (pintype "passive"))
    )
    (net (code "131") (name "unconnected-(SV6-Pad22)") (class "Default")
      (node (ref "SV6") (pin "22") (pinfunction "22_22") (pintype "passive"))
    )
    (net (code "132") (name "unconnected-(SV6-Pad26)") (class "Default")
      (node (ref "SV6") (pin "26") (pinfunction "26_26") (pintype "passive"))
    )
    (net (code "133") (name "unconnected-(SV6-Pad34)") (class "Default")
      (node (ref "SV6") (pin "34") (pinfunction "34_34") (pintype "passive"))
    )
    (net (code "134") (name "unconnected-(SV7-Pad2)") (class "Default")
      (node (ref "SV7") (pin "2") (pinfunction "2_2") (pintype "passive"))
    )
    (net (code "135") (name "unconnected-(SV7-Pad4)") (class "Default")
      (node (ref "SV7") (pin "4") (pinfunction "4_4") (pintype "passive"))
    )
    (net (code "136") (name "unconnected-(SV7-Pad10)") (class "Default")
      (node (ref "SV7") (pin "10") (pinfunction "10_10") (pintype "passive"))
    )
    (net (code "137") (name "unconnected-(SV7-Pad14)") (class "Default")
      (node (ref "SV7") (pin "14") (pinfunction "14_14") (pintype "passive"))
    )
    (net (code "138") (name "unconnected-(SV7-Pad18)") (class "Default")
      (node (ref "SV7") (pin "18") (pinfunction "18_18") (pintype "passive"))
    )
    (net (code "139") (name "unconnected-(SV7-Pad22)") (class "Default")
      (node (ref "SV7") (pin "22") (pinfunction "22_22") (pintype "passive"))
    )
    (net (code "140") (name "unconnected-(SV7-Pad26)") (class "Default")
      (node (ref "SV7") (pin "26") (pinfunction "26_26") (pintype "passive"))
    )
    (net (code "141") (name "unconnected-(SV7-Pad34)") (class "Default")
      (node (ref "SV7") (pin "34") (pinfunction "34_34") (pintype "passive"))
    )
    (net (code "142") (name "unconnected-(SV8-Pad2)") (class "Default")
      (node (ref "SV8") (pin "2") (pinfunction "2_2") (pintype "passive"))
    )
    (net (code "143") (name "unconnected-(SV8-Pad4)") (class "Default")
      (node (ref "SV8") (pin "4") (pinfunction "4_4") (pintype "passive"))
    )
    (net (code "144") (name "unconnected-(SV8-Pad10)") (class "Default")
      (node (ref "SV8") (pin "10") (pinfunction "10_10") (pintype "passive"))
    )
    (net (code "145") (name "unconnected-(SV8-Pad14)") (class "Default")
      (node (ref "SV8") (pin "14") (pinfunction "14_14") (pintype "passive"))
    )
    (net (code "146") (name "unconnected-(SV8-Pad18)") (class "Default")
      (node (ref "SV8") (pin "18") (pinfunction "18_18") (pintype "passive"))
    )
    (net (code "147") (name "unconnected-(SV8-Pad22)") (class "Default")
      (node (ref "SV8") (pin "22") (pinfunction "22_22") (pintype "passive"))
    )
    (net (code "148") (name "unconnected-(SV8-Pad26)") (class "Default")
      (node (ref "SV8") (pin "26") (pinfunction "26_26") (pintype "passive"))
    )
    (net (code "149") (name "unconnected-(SV8-Pad34)") (class "Default")
      (node (ref "SV8") (pin "34") (pinfunction "34_34") (pintype "passive"))
    )
    (net (code "150") (name "unconnected-(SV9-Pad2)") (class "Default")
      (node (ref "SV9") (pin "2") (pinfunction "2_2") (pintype "passive"))
    )
    (net (code "151") (name "unconnected-(SV9-Pad4)") (class "Default")
      (node (ref "SV9") (pin "4") (pinfunction "4_4") (pintype "passive"))
    )
    (net (code "152") (name "unconnected-(SV9-Pad10)") (class "Default")
      (node (ref "SV9") (pin "10") (pinfunction "10_10") (pintype "passive"))
    )
    (net (code "153") (name "unconnected-(SV9-Pad14)") (class "Default")
      (node (ref "SV9") (pin "14") (pinfunction "14_14") (pintype "passive"))
    )
    (net (code "154") (name "unconnected-(SV9-Pad18)") (class "Default")
      (node (ref "SV9") (pin "18") (pinfunction "18_18") (pintype "passive"))
    )
    (net (code "155") (name "unconnected-(SV9-Pad22)") (class "Default")
      (node (ref "SV9") (pin "22") (pinfunction "22_22") (pintype "passive"))
    )
    (net (code "156") (name "unconnected-(SV9-Pad26)") (class "Default")
      (node (ref "SV9") (pin "26") (pinfunction "26_26") (pintype "passive"))
    )
    (net (code "157") (name "unconnected-(SV9-Pad34)") (class "Default")
      (node (ref "SV9") (pin "34") (pinfunction "34_34") (pintype "passive"))
    )
    (net (code "158") (name "unconnected-(SV10-Pad2)") (class "Default")
      (node (ref "SV10") (pin "2") (pinfunction "2_2") (pintype "passive"))
    )
    (net (code "159") (name "unconnected-(SV10-Pad4)") (class "Default")
      (node (ref "SV10") (pin "4") (pinfunction "4_4") (pintype "passive"))
    )
    (net (code "160") (name "unconnected-(SV10-Pad10)") (class "Default")
      (node (ref "SV10") (pin "10") (pinfunction "10_10") (pintype "passive"))
    )
    (net (code "161") (name "unconnected-(SV10-Pad14)") (class "Default")
      (node (ref "SV10") (pin "14") (pinfunction "14_14") (pintype "passive"))
    )
    (net (code "162") (name "unconnected-(SV10-Pad18)") (class "Default")
      (node (ref "SV10") (pin "18") (pinfunction "18_18") (pintype "passive"))
    )
    (net (code "163") (name "unconnected-(SV10-Pad22)") (class "Default")
      (node (ref "SV10") (pin "22") (pinfunction "22_22") (pintype "passive"))
    )
    (net (code "164") (name "unconnected-(SV10-Pad26)") (class "Default")
      (node (ref "SV10") (pin "26") (pinfunction "26_26") (pintype "passive"))
    )
    (net (code "165") (name "unconnected-(SV10-Pad34)") (class "Default")
      (node (ref "SV10") (pin "34") (pinfunction "34_34") (pintype "passive"))
    )
    (net (code "166") (name "unconnected-(SV11-Pad2)") (class "Default")
      (node (ref "SV11") (pin "2") (pinfunction "2_2") (pintype "passive"))
    )
    (net (code "167") (name "unconnected-(SV11-Pad4)") (class "Default")
      (node (ref "SV11") (pin "4") (pinfunction "4_4") (pintype "passive"))
    )
    (net (code "168") (name "unconnected-(SV11-Pad10)") (class "Default")
      (node (ref "SV11") (pin "10") (pinfunction "10_10") (pintype "passive"))
    )
    (net (code "169") (name "unconnected-(SV11-Pad14)") (class "Default")
      (node (ref "SV11") (pin "14") (pinfunction "14_14") (pintype "passive"))
    )
    (net (code "170") (name "unconnected-(SV11-Pad18)") (class "Default")
      (node (ref "SV11") (pin "18") (pinfunction "18_18") (pintype "passive"))
    )
    (net (code "171") (name "unconnected-(SV11-Pad22)") (class "Default")
      (node (ref "SV11") (pin "22") (pinfunction "22_22") (pintype "passive"))
    )
    (net (code "172") (name "unconnected-(SV11-Pad26)") (class "Default")
      (node (ref "SV11") (pin "26") (pinfunction "26_26") (pintype "passive"))
    )
    (net (code "173") (name "unconnected-(SV11-Pad34)") (class "Default")
      (node (ref "SV11") (pin "34") (pinfunction "34_34") (pintype "passive"))
    )
    (net (code "174") (name "unconnected-(SV12-Pad2)") (class "Default")
      (node (ref "SV12") (pin "2") (pinfunction "2_2") (pintype "passive"))
    )
    (net (code "175") (name "unconnected-(SV12-Pad4)") (class "Default")
      (node (ref "SV12") (pin "4") (pinfunction "4_4") (pintype "passive"))
    )
    (net (code "176") (name "unconnected-(SV12-Pad10)") (class "Default")
      (node (ref "SV12") (pin "10") (pinfunction "10_10") (pintype "passive"))
    )
    (net (code "177") (name "unconnected-(SV12-Pad14)") (class "Default")
      (node (ref "SV12") (pin "14") (pinfunction "14_14") (pintype "passive"))
    )
    (net (code "178") (name "unconnected-(SV12-Pad18)") (class "Default")
      (node (ref "SV12") (pin "18") (pinfunction "18_18") (pintype "passive"))
    )
    (net (code "179") (name "unconnected-(SV12-Pad22)") (class "Default")
      (node (ref "SV12") (pin "22") (pinfunction "22_22") (pintype "passive"))
    )
    (net (code "180") (name "unconnected-(SV12-Pad26)") (class "Default")
      (node (ref "SV12") (pin "26") (pinfunction "26_26") (pintype "passive"))
    )
    (net (code "181") (name "unconnected-(SV12-Pad34)") (class "Default")
      (node (ref "SV12") (pin "34") (pinfunction "34_34") (pintype "passive"))
    )
  )
)
